# PIC32_board.net
KiCad netlist of a schematic drawn in EAGLE
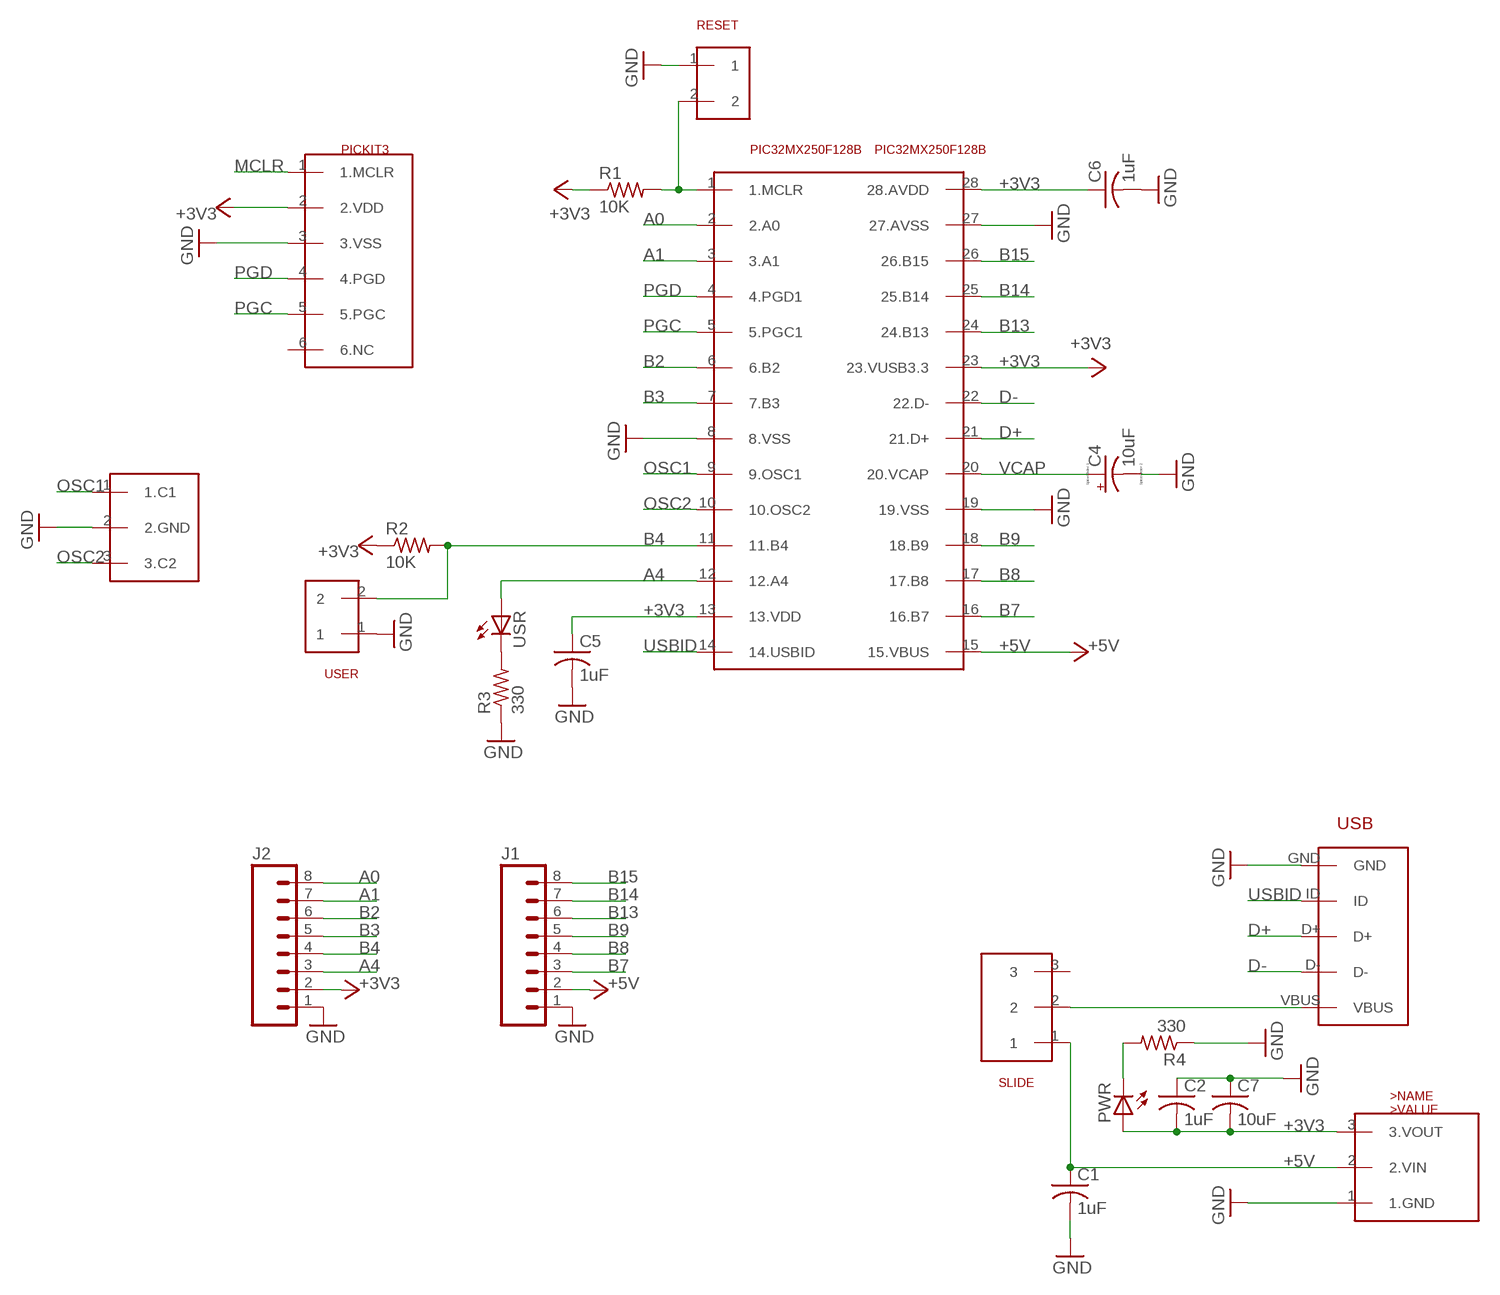
[diagram p0: schematic, sheet 1]

(export (version "E")
  (design (tool "Eeschema 10.0.6"))
  (components
    (comp (ref "C1")
      (value "1uF")
      (footprint "eagle-import:C025-024X044")
      (libsource (lib "eagle-import") (part "C-US025-024X044"))
    )
    (comp (ref "C2")
      (value "1uF")
      (footprint "eagle-import:C025-024X044")
      (libsource (lib "eagle-import") (part "C-US025-024X044"))
    )
    (comp (ref "C4")
      (value "10uF")
      (footprint "eagle-import:B45181B")
      (libsource (lib "eagle-import") (part "CPOL-USB45181B"))
    )
    (comp (ref "C5")
      (value "1uF")
      (footprint "eagle-import:C025-024X044")
      (libsource (lib "eagle-import") (part "C-US025-024X044"))
    )
    (comp (ref "C6")
      (value "1uF")
      (footprint "eagle-import:C025-024X044")
      (libsource (lib "eagle-import") (part "C-US025-024X044"))
    )
    (comp (ref "C7")
      (value "10uF")
      (footprint "eagle-import:C025-024X044")
      (libsource (lib "eagle-import") (part "C-US025-024X044"))
    )
    (comp (ref "J1")
      (value "M08")
      (footprint "eagle-import:1X08_ROUND")
      (libsource (lib "eagle-import") (part "M08"))
    )
    (comp (ref "J2")
      (value "M08")
      (footprint "eagle-import:1X08_ROUND")
      (libsource (lib "eagle-import") (part "M08"))
    )
    (comp (ref "OSC")
      (value "OSC")
      (footprint "eagle-import:1X03")
      (libsource (lib "eagle-import") (part "OSC"))
    )
    (comp (ref "PIC32MX250F128B")
      (value "PIC32MX250F128B")
      (footprint "eagle-import:DIL28-3")
      (libsource (lib "eagle-import") (part "PIC32"))
    )
    (comp (ref "PICKIT3")
      (value "PICKIT3")
      (footprint "eagle-import:1X06")
      (libsource (lib "eagle-import") (part "PICKIT3"))
    )
    (comp (ref "PWR")
      (value "LED3MM")
      (footprint "eagle-import:LED3MM")
      (libsource (lib "eagle-import") (part "LED3MM"))
    )
    (comp (ref "R1")
      (value "10K")
      (footprint "eagle-import:0207_10")
      (libsource (lib "eagle-import") (part "R-US_0207/10"))
    )
    (comp (ref "R2")
      (value "10K")
      (footprint "eagle-import:0207_10")
      (libsource (lib "eagle-import") (part "R-US_0207/10"))
    )
    (comp (ref "R3")
      (value "330")
      (footprint "eagle-import:0207_10")
      (libsource (lib "eagle-import") (part "R-US_0207/10"))
    )
    (comp (ref "R4")
      (value "330")
      (footprint "eagle-import:0207_10")
      (libsource (lib "eagle-import") (part "R-US_0207/10"))
    )
    (comp (ref "RESET")
      (value "PUSHBUTTON")
      (footprint "eagle-import:PUSHBUTTON")
      (libsource (lib "eagle-import") (part "PUSHBUTTON"))
    )
    (comp (ref "SLIDE")
      (value "SLIDE")
      (footprint "eagle-import:SLIDE")
      (libsource (lib "eagle-import") (part "SLIDE"))
    )
    (comp (ref "U$3")
      (value "MCP1702")
      (footprint "eagle-import:TO92")
      (libsource (lib "eagle-import") (part "MCP1702"))
    )
    (comp (ref "USB")
      (value "USB_5PIN")
      (footprint "eagle-import:USB-MB-H")
      (libsource (lib "eagle-import") (part "USB_5PIN"))
    )
    (comp (ref "USER")
      (value "PUSHBUTTON")
      (footprint "eagle-import:PUSHBUTTON")
      (libsource (lib "eagle-import") (part "PUSHBUTTON"))
    )
    (comp (ref "USR")
      (value "LED3MM")
      (footprint "eagle-import:LED3MM")
      (libsource (lib "eagle-import") (part "LED3MM"))
    )
  )
  (nets
    (net (code "1") (name "+3V3") (class "Default")
      (node (ref "C2") (pin "2") (pinfunction "2_2") (pintype "passive"))
      (node (ref "C5") (pin "1") (pinfunction "1_1") (pintype "passive"))
      (node (ref "C6") (pin "1") (pinfunction "1_1") (pintype "passive"))
      (node (ref "C7") (pin "2") (pinfunction "2_2") (pintype "passive"))
      (node (ref "J2") (pin "2") (pinfunction "2_2") (pintype "passive"))
      (node (ref "PIC32MX250F128B") (pin "13") (pinfunction "13.VDD_13") (pintype "bidirectional"))
      (node (ref "PIC32MX250F128B") (pin "23") (pinfunction "23.VUSB3.3_23") (pintype "bidirectional"))
      (node (ref "PIC32MX250F128B") (pin "28") (pinfunction "28.AVDD_28") (pintype "bidirectional"))
      (node (ref "PICKIT3") (pin "2") (pinfunction "2.VDD_2") (pintype "bidirectional"))
      (node (ref "PWR") (pin "A") (pinfunction "A_A") (pintype "passive"))
      (node (ref "R1") (pin "1") (pinfunction "1_1") (pintype "passive"))
      (node (ref "R2") (pin "1") (pinfunction "1_1") (pintype "passive"))
      (node (ref "U$3") (pin "3") (pinfunction "3.VOUT_3") (pintype "bidirectional"))
    )
    (net (code "2") (name "+5V") (class "Default")
      (node (ref "C1") (pin "1") (pinfunction "1_1") (pintype "passive"))
      (node (ref "J1") (pin "2") (pinfunction "2_2") (pintype "passive"))
      (node (ref "PIC32MX250F128B") (pin "15") (pinfunction "15.VBUS_15") (pintype "bidirectional"))
      (node (ref "SLIDE") (pin "1") (pinfunction "1_1") (pintype "bidirectional"))
      (node (ref "U$3") (pin "2") (pinfunction "2.VIN_2") (pintype "bidirectional"))
    )
    (net (code "3") (name "/A0") (class "Default")
      (node (ref "J2") (pin "8") (pinfunction "8_8") (pintype "passive"))
      (node (ref "PIC32MX250F128B") (pin "2") (pinfunction "2.A0_2") (pintype "bidirectional"))
    )
    (net (code "4") (name "/A1") (class "Default")
      (node (ref "J2") (pin "7") (pinfunction "7_7") (pintype "passive"))
      (node (ref "PIC32MX250F128B") (pin "3") (pinfunction "3.A1_3") (pintype "bidirectional"))
    )
    (net (code "5") (name "/A4") (class "Default")
      (node (ref "J2") (pin "3") (pinfunction "3_3") (pintype "passive"))
      (node (ref "PIC32MX250F128B") (pin "12") (pinfunction "12.A4_12") (pintype "bidirectional"))
      (node (ref "USR") (pin "A") (pinfunction "A_A") (pintype "passive"))
    )
    (net (code "6") (name "/B2") (class "Default")
      (node (ref "J2") (pin "6") (pinfunction "6_6") (pintype "passive"))
      (node (ref "PIC32MX250F128B") (pin "6") (pinfunction "6.B2_6") (pintype "bidirectional"))
    )
    (net (code "7") (name "/B3") (class "Default")
      (node (ref "J2") (pin "5") (pinfunction "5_5") (pintype "passive"))
      (node (ref "PIC32MX250F128B") (pin "7") (pinfunction "7.B3_7") (pintype "bidirectional"))
    )
    (net (code "8") (name "/B4") (class "Default")
      (node (ref "J2") (pin "4") (pinfunction "4_4") (pintype "passive"))
      (node (ref "PIC32MX250F128B") (pin "11") (pinfunction "11.B4_11") (pintype "bidirectional"))
      (node (ref "R2") (pin "2") (pinfunction "2_2") (pintype "passive"))
      (node (ref "USER") (pin "2") (pinfunction "2_2") (pintype "bidirectional"))
    )
    (net (code "9") (name "/B7") (class "Default")
      (node (ref "J1") (pin "3") (pinfunction "3_3") (pintype "passive"))
      (node (ref "PIC32MX250F128B") (pin "16") (pinfunction "16.B7_16") (pintype "bidirectional"))
    )
    (net (code "10") (name "/B8") (class "Default")
      (node (ref "J1") (pin "4") (pinfunction "4_4") (pintype "passive"))
      (node (ref "PIC32MX250F128B") (pin "17") (pinfunction "17.B8_17") (pintype "bidirectional"))
    )
    (net (code "11") (name "/B9") (class "Default")
      (node (ref "J1") (pin "5") (pinfunction "5_5") (pintype "passive"))
      (node (ref "PIC32MX250F128B") (pin "18") (pinfunction "18.B9_18") (pintype "bidirectional"))
    )
    (net (code "12") (name "/B13") (class "Default")
      (node (ref "J1") (pin "6") (pinfunction "6_6") (pintype "passive"))
      (node (ref "PIC32MX250F128B") (pin "24") (pinfunction "24.B13_24") (pintype "bidirectional"))
    )
    (net (code "13") (name "/B14") (class "Default")
      (node (ref "J1") (pin "7") (pinfunction "7_7") (pintype "passive"))
      (node (ref "PIC32MX250F128B") (pin "25") (pinfunction "25.B14_25") (pintype "bidirectional"))
    )
    (net (code "14") (name "/B15") (class "Default")
      (node (ref "J1") (pin "8") (pinfunction "8_8") (pintype "passive"))
      (node (ref "PIC32MX250F128B") (pin "26") (pinfunction "26.B15_26") (pintype "bidirectional"))
    )
    (net (code "15") (name "/D+") (class "Default")
      (node (ref "PIC32MX250F128B") (pin "21") (pinfunction "21.D+_21") (pintype "bidirectional"))
      (node (ref "USB") (pin "D+") (pinfunction "D+_D+") (pintype "bidirectional"))
    )
    (net (code "16") (name "/D-") (class "Default")
      (node (ref "PIC32MX250F128B") (pin "22") (pinfunction "22.D-_22") (pintype "bidirectional"))
      (node (ref "USB") (pin "D-") (pinfunction "D-_D-") (pintype "bidirectional"))
    )
    (net (code "17") (name "/MCLR") (class "Default")
      (node (ref "PIC32MX250F128B") (pin "1") (pinfunction "1.MCLR_1") (pintype "bidirectional"))
      (node (ref "PICKIT3") (pin "1") (pinfunction "1.MCLR_1") (pintype "bidirectional"))
      (node (ref "R1") (pin "2") (pinfunction "2_2") (pintype "passive"))
      (node (ref "RESET") (pin "2") (pinfunction "2_2") (pintype "bidirectional"))
    )
    (net (code "18") (name "/OSC1") (class "Default")
      (node (ref "OSC") (pin "1") (pinfunction "1.C1_1") (pintype "bidirectional"))
      (node (ref "PIC32MX250F128B") (pin "9") (pinfunction "9.OSC1_9") (pintype "bidirectional"))
    )
    (net (code "19") (name "/OSC2") (class "Default")
      (node (ref "OSC") (pin "3") (pinfunction "3.C2_3") (pintype "bidirectional"))
      (node (ref "PIC32MX250F128B") (pin "10") (pinfunction "10.OSC2_10") (pintype "bidirectional"))
    )
    (net (code "20") (name "/PGC") (class "Default")
      (node (ref "PIC32MX250F128B") (pin "5") (pinfunction "5.PGC1_5") (pintype "bidirectional"))
      (node (ref "PICKIT3") (pin "5") (pinfunction "5.PGC_5") (pintype "bidirectional"))
    )
    (net (code "21") (name "/PGD") (class "Default")
      (node (ref "PIC32MX250F128B") (pin "4") (pinfunction "4.PGD1_4") (pintype "bidirectional"))
      (node (ref "PICKIT3") (pin "4") (pinfunction "4.PGD_4") (pintype "bidirectional"))
    )
    (net (code "22") (name "/USBID") (class "Default")
      (node (ref "PIC32MX250F128B") (pin "14") (pinfunction "14.USBID_14") (pintype "bidirectional"))
      (node (ref "USB") (pin "ID") (pinfunction "ID_ID") (pintype "bidirectional"))
    )
    (net (code "23") (name "/VCAP") (class "Default")
      (node (ref "C4") (pin "+") (pinfunction "+_+") (pintype "passive"))
      (node (ref "PIC32MX250F128B") (pin "20") (pinfunction "20.VCAP_20") (pintype "bidirectional"))
    )
    (net (code "24") (name "GND") (class "Default")
      (node (ref "C1") (pin "2") (pinfunction "2_2") (pintype "passive"))
      (node (ref "C2") (pin "1") (pinfunction "1_1") (pintype "passive"))
      (node (ref "C4") (pin "-") (pinfunction "-_-") (pintype "passive"))
      (node (ref "C5") (pin "2") (pinfunction "2_2") (pintype "passive"))
      (node (ref "C6") (pin "2") (pinfunction "2_2") (pintype "passive"))
      (node (ref "C7") (pin "1") (pinfunction "1_1") (pintype "passive"))
      (node (ref "J1") (pin "1") (pinfunction "1_1") (pintype "passive"))
      (node (ref "J2") (pin "1") (pinfunction "1_1") (pintype "passive"))
      (node (ref "OSC") (pin "2") (pinfunction "2.GND_2") (pintype "bidirectional"))
      (node (ref "PIC32MX250F128B") (pin "19") (pinfunction "19.VSS_19") (pintype "bidirectional"))
      (node (ref "PIC32MX250F128B") (pin "27") (pinfunction "27.AVSS_27") (pintype "bidirectional"))
      (node (ref "PIC32MX250F128B") (pin "8") (pinfunction "8.VSS_8") (pintype "bidirectional"))
      (node (ref "PICKIT3") (pin "3") (pinfunction "3.VSS_3") (pintype "bidirectional"))
      (node (ref "R3") (pin "1") (pinfunction "1_1") (pintype "passive"))
      (node (ref "R4") (pin "1") (pinfunction "1_1") (pintype "passive"))
      (node (ref "RESET") (pin "1") (pinfunction "1_1") (pintype "bidirectional"))
      (node (ref "U$3") (pin "1") (pinfunction "1.GND_1") (pintype "bidirectional"))
      (node (ref "USB") (pin "GND") (pinfunction "GND_GND") (pintype "bidirectional"))
      (node (ref "USER") (pin "1") (pinfunction "1_1") (pintype "bidirectional"))
    )
    (net (code "25") (name "Net-(PWR-C)") (class "Default")
      (node (ref "PWR") (pin "K") (pinfunction "C_K") (pintype "passive"))
      (node (ref "R4") (pin "2") (pinfunction "2_2") (pintype "passive"))
    )
    (net (code "26") (name "Net-(SLIDE-Pad2)") (class "Default")
      (node (ref "SLIDE") (pin "2") (pinfunction "2_2") (pintype "bidirectional"))
      (node (ref "USB") (pin "VBUS") (pinfunction "VBUS_VBUS") (pintype "bidirectional"))
    )
    (net (code "27") (name "Net-(USR-C)") (class "Default")
      (node (ref "R3") (pin "2") (pinfunction "2_2") (pintype "passive"))
      (node (ref "USR") (pin "K") (pinfunction "C_K") (pintype "passive"))
    )
    (net (code "28") (name "unconnected-(PICKIT3-6.NC-Pad6)") (class "Default")
      (node (ref "PICKIT3") (pin "6") (pinfunction "6.NC_6") (pintype "bidirectional"))
    )
    (net (code "29") (name "unconnected-(SLIDE-Pad3)") (class "Default")
      (node (ref "SLIDE") (pin "3") (pinfunction "3_3") (pintype "bidirectional"))
    )
  )
)
